# VREG_AOZ1021AI_4V2_3A.net
KiCad netlist of a schematic drawn in Altium Designer
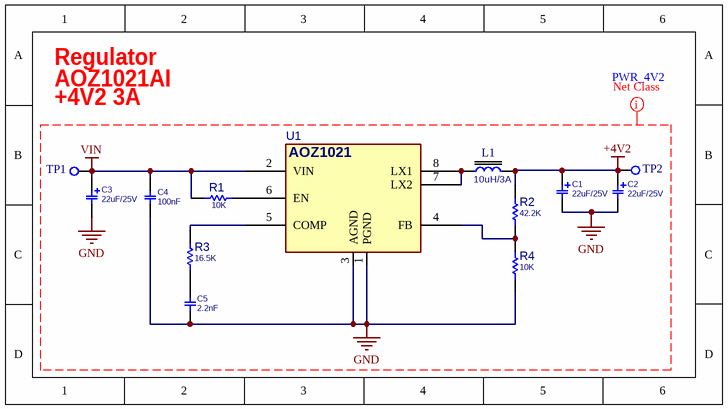
[diagram p0: VREG AOZ1021AI +4V2 3A.SchDoc]

(export (version "E")
  (design (tool "Eeschema 10.0.6"))
  (components
    (comp (ref "C1")
      (value "22uF/25V")
      (footprint "C_TN_3216")
      (description "CAP, SMD, TAN")
      (libsource (lib "Passive") (part "CAP_SMD_TAN"))
    )
    (comp (ref "C2")
      (value "22uF/25V")
      (footprint "C_TN_3216")
      (description "CAP, SMD, TAN")
      (libsource (lib "Passive") (part "CAP_SMD_TAN"))
    )
    (comp (ref "C3")
      (value "22uF/25V")
      (footprint "C_TN_3216")
      (description "CAP, SMD, TAN")
      (libsource (lib "Passive") (part "CAP_SMD_TAN"))
    )
    (comp (ref "C4")
      (value "100nF")
      (footprint "C0603S")
      (description "CAP, SMD, MLCC")
      (fields (field (name "MANF_P#") "MANF_PART#") (field (name "MANF") "Murata"))
      (libsource (lib "Passive") (part "CAP_SMD_MLCC"))
    )
    (comp (ref "C5")
      (value "2.2nF")
      (footprint "C0603S")
      (description "CAP, SMD, MLCC")
      (fields (field (name "MANF_P#") "MANF_PART#") (field (name "MANF") "Murata"))
      (libsource (lib "Passive") (part "CAP_SMD_MLCC"))
    )
    (comp (ref "L1")
      (value "10uH/3A")
      (footprint "L_8")
      (description "IND, PWR, SMD")
      (libsource (lib "Passive") (part "INDPWR_SMD"))
    )
    (comp (ref "R1")
      (value "10K")
      (footprint "R0603S")
      (description "RES, SMD")
      (fields (field (name "MANF_P#") "RK73H1ETTP4701F") (field (name "MANF") "KOA SPEER"))
      (libsource (lib "Passive") (part "RES_SMD"))
    )
    (comp (ref "R2")
      (value "42.2K")
      (footprint "R0603S")
      (description "RES, SMD")
      (fields (field (name "MANF_P#") "RK73H1ETTP4701F") (field (name "MANF") "KOA SPEER"))
      (libsource (lib "Passive") (part "RES_SMD"))
    )
    (comp (ref "R3")
      (value "16.5K")
      (footprint "R0603S")
      (description "RES, SMD")
      (fields (field (name "MANF_P#") "RK73H1ETTP4701F") (field (name "MANF") "KOA SPEER"))
      (libsource (lib "Passive") (part "RES_SMD"))
    )
    (comp (ref "R4")
      (value "10K")
      (footprint "R0603S")
      (description "RES, SMD")
      (fields (field (name "MANF_P#") "RK73H1ETTP4701F") (field (name "MANF") "KOA SPEER"))
      (libsource (lib "Passive") (part "RES_SMD"))
    )
    (comp (ref "TP1")
      (value "Test Point")
      (footprint "TPSMD_C1")
      (libsource (lib "PW Components") (part "Test Point"))
    )
    (comp (ref "TP2")
      (value "Test Point")
      (footprint "TPSMD_C1")
      (libsource (lib "PW Components") (part "Test Point"))
    )
    (comp (ref "U1")
      (value "AOZ1021AI")
      (footprint "SO_8")
      (description "REG, Switching, Buck, 3A, ADJ, 500KHz, 4.5~16VIN, SO-8")
      (fields (field (name "MANF") "AOSMD"))
      (libsource (lib "PW Components") (part "VREG_AOZ1021AI_SO8"))
    )
  )
  (nets
    (net (code "1") (name "+4V2") (class "Default")
      (node (ref "C1") (pin "1") (pinfunction "1_1") (pintype "passive"))
      (node (ref "C2") (pin "1") (pinfunction "1_1") (pintype "passive"))
      (node (ref "L1") (pin "2") (pinfunction "2_2") (pintype "passive"))
      (node (ref "R2") (pin "1") (pinfunction "1_1") (pintype "passive"))
      (node (ref "TP2") (pin "1") (pinfunction "TP_1") (pintype "passive"))
    )
    (net (code "2") (name "GND") (class "Default")
      (node (ref "C1") (pin "2") (pinfunction "2_2") (pintype "passive"))
      (node (ref "C2") (pin "2") (pinfunction "2_2") (pintype "passive"))
      (node (ref "C3") (pin "2") (pinfunction "2_2") (pintype "passive"))
      (node (ref "C4") (pin "1") (pinfunction "1_1") (pintype "passive"))
      (node (ref "C5") (pin "1") (pinfunction "1_1") (pintype "passive"))
      (node (ref "R4") (pin "2") (pinfunction "2_2") (pintype "passive"))
      (node (ref "U1") (pin "1") (pinfunction "PGND_1") (pintype "power_in"))
      (node (ref "U1") (pin "3") (pinfunction "AGND_3") (pintype "power_in"))
    )
    (net (code "3") (name "Net-(C5-Pad2)") (class "Default")
      (node (ref "C5") (pin "2") (pinfunction "2_2") (pintype "passive"))
      (node (ref "R3") (pin "2") (pinfunction "2_2") (pintype "passive"))
    )
    (net (code "4") (name "Net-(U1-COMP)") (class "Default")
      (node (ref "R3") (pin "1") (pinfunction "1_1") (pintype "passive"))
      (node (ref "U1") (pin "5") (pinfunction "COMP_5") (pintype "passive"))
    )
    (net (code "5") (name "Net-(U1-EN)") (class "Default")
      (node (ref "R1") (pin "1") (pinfunction "1_1") (pintype "passive"))
      (node (ref "U1") (pin "6") (pinfunction "EN_6") (pintype "passive"))
    )
    (net (code "6") (name "Net-(U1-FB)") (class "Default")
      (node (ref "R2") (pin "2") (pinfunction "2_2") (pintype "passive"))
      (node (ref "R4") (pin "1") (pinfunction "1_1") (pintype "passive"))
      (node (ref "U1") (pin "4") (pinfunction "FB_4") (pintype "passive"))
    )
    (net (code "7") (name "Net-(U1-LX1)") (class "Default")
      (node (ref "L1") (pin "1") (pinfunction "1_1") (pintype "passive"))
      (node (ref "U1") (pin "7") (pinfunction "LX2_7") (pintype "passive"))
      (node (ref "U1") (pin "8") (pinfunction "LX1_8") (pintype "passive"))
    )
    (net (code "8") (name "VIN") (class "Default")
      (node (ref "C3") (pin "1") (pinfunction "1_1") (pintype "passive"))
      (node (ref "C4") (pin "2") (pinfunction "2_2") (pintype "passive"))
      (node (ref "R1") (pin "2") (pinfunction "2_2") (pintype "passive"))
      (node (ref "TP1") (pin "1") (pinfunction "TP_1") (pintype "passive"))
      (node (ref "U1") (pin "2") (pinfunction "VIN_2") (pintype "power_in"))
    )
  )
)
